# relay.net
KiCad netlist of a schematic drawn in EAGLE
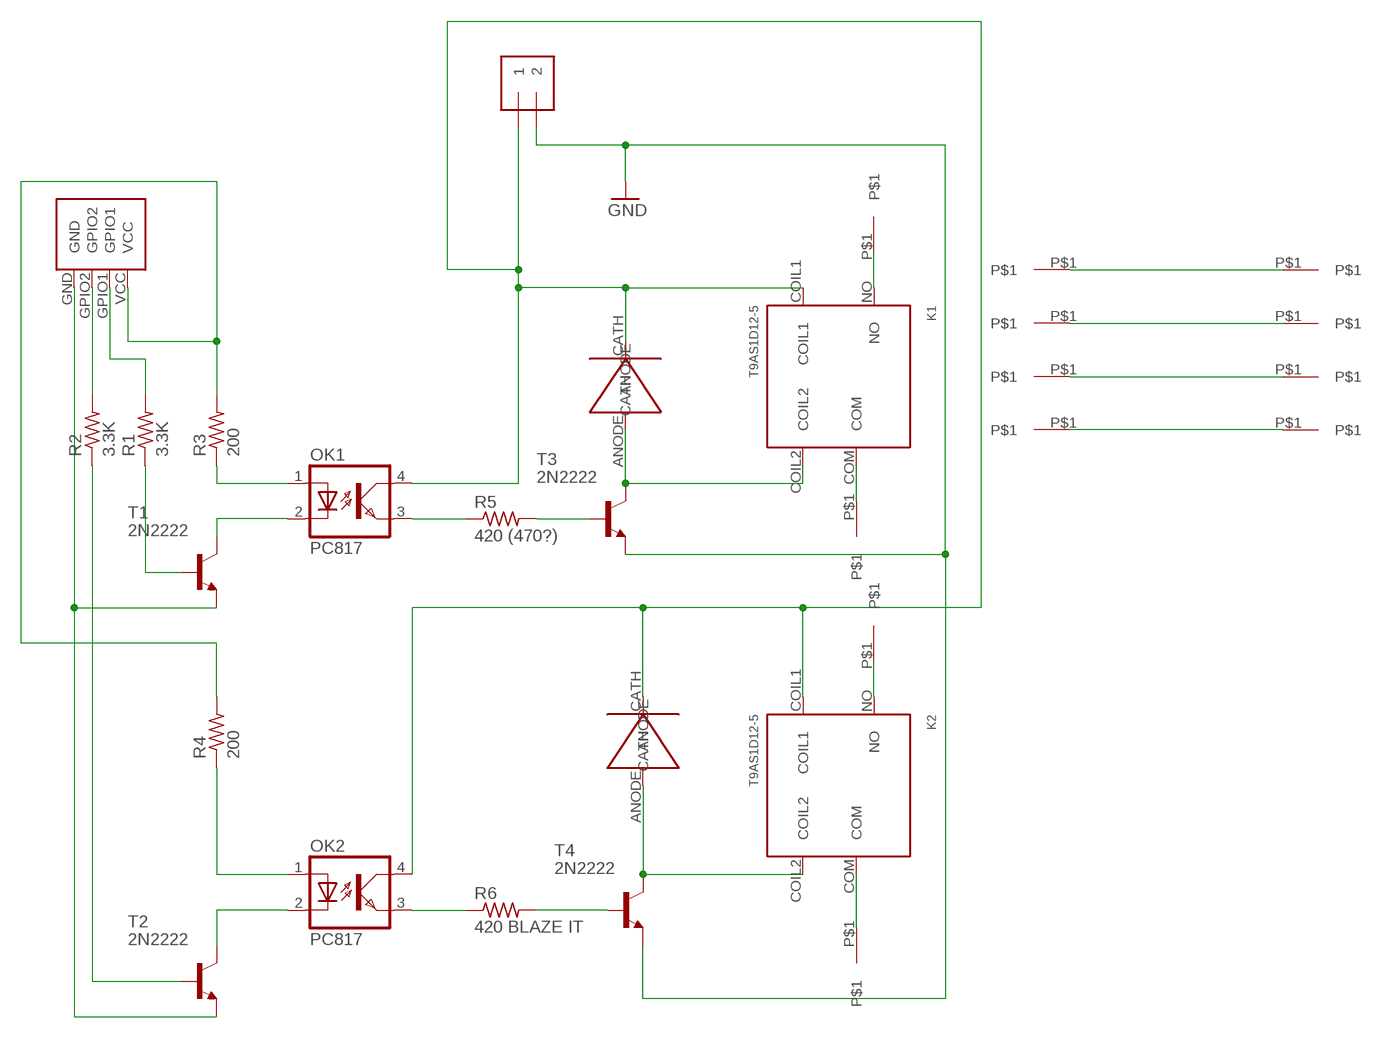
[diagram p0: schematic, sheet 1]

(export (version "E")
  (design (tool "Eeschema 10.0.6"))
  (components
    (comp (ref "J1")
      (value "1X2-3.5MM")
      (footprint "eagle-import:1X2-3.5MM")
      (libsource (lib "eagle-import") (part "1X2-3.5MM"))
    )
    (comp (ref "K1")
      (value "T9AS1D12-5")
      (footprint "eagle-import:T9AS1D12-5")
      (libsource (lib "eagle-import") (part "T9AS1D12-5"))
    )
    (comp (ref "K2")
      (value "T9AS1D12-5")
      (footprint "eagle-import:T9AS1D12-5")
      (libsource (lib "eagle-import") (part "T9AS1D12-5"))
    )
    (comp (ref "OK1")
      (value "PC817")
      (footprint "eagle-import:DIL04")
      (fields (field (name "MPN") "PC817X4J000F"))
      (libsource (lib "eagle-import") (part "PC817"))
    )
    (comp (ref "OK2")
      (value "PC817")
      (footprint "eagle-import:DIL04")
      (fields (field (name "MPN") "PC817X4J000F"))
      (libsource (lib "eagle-import") (part "PC817"))
    )
    (comp (ref "R1")
      (value "3.3K")
      (footprint "eagle-import:R0805")
      (libsource (lib "eagle-import") (part "R-US_R0805"))
    )
    (comp (ref "R2")
      (value "3.3K")
      (footprint "eagle-import:R0805")
      (libsource (lib "eagle-import") (part "R-US_R0805"))
    )
    (comp (ref "R3")
      (value "200")
      (footprint "eagle-import:R0805")
      (libsource (lib "eagle-import") (part "R-US_R0805"))
    )
    (comp (ref "R4")
      (value "200")
      (footprint "eagle-import:R0805")
      (libsource (lib "eagle-import") (part "R-US_R0805"))
    )
    (comp (ref "R5")
      (value "420 (470?)")
      (footprint "eagle-import:R0805")
      (libsource (lib "eagle-import") (part "R-US_R0805"))
    )
    (comp (ref "R6")
      (value "420 BLAZE IT")
      (footprint "eagle-import:R0805")
      (libsource (lib "eagle-import") (part "R-US_R0805"))
    )
    (comp (ref "T1")
      (value "2N2222")
      (footprint "eagle-import:TO92-EBC-OVAL")
      (libsource (lib "eagle-import") (part "2N2222"))
    )
    (comp (ref "T2")
      (value "2N2222")
      (footprint "eagle-import:TO92-EBC-OVAL")
      (libsource (lib "eagle-import") (part "2N2222"))
    )
    (comp (ref "T3")
      (value "2N2222")
      (footprint "eagle-import:TO92-EBC-OVAL")
      (libsource (lib "eagle-import") (part "2N2222"))
    )
    (comp (ref "T4")
      (value "2N2222")
      (footprint "eagle-import:TO92-EBC-OVAL")
      (libsource (lib "eagle-import") (part "2N2222"))
    )
    (comp (ref "U$1")
      (value "MTA-156")
      (footprint "eagle-import:MTA-156_HEADER")
      (libsource (lib "eagle-import") (part "MTA-156"))
    )
    (comp (ref "U$2")
      (value "VTB8441BH")
      (footprint "eagle-import:VTB8441BH")
      (libsource (lib "eagle-import") (part "VTB8441BH"))
    )
    (comp (ref "U$3")
      (value "VTB8441BH")
      (footprint "eagle-import:VTB8441BH")
      (libsource (lib "eagle-import") (part "VTB8441BH"))
    )
    (comp (ref "U$4")
      (value "MAIN")
      (footprint "eagle-import:MAIN")
      (libsource (lib "eagle-import") (part "MAIN"))
    )
    (comp (ref "U$5")
      (value "MAIN")
      (footprint "eagle-import:MAIN")
      (libsource (lib "eagle-import") (part "MAIN"))
    )
    (comp (ref "U$6")
      (value "MAIN")
      (footprint "eagle-import:MAIN")
      (libsource (lib "eagle-import") (part "MAIN"))
    )
    (comp (ref "U$7")
      (value "MAIN")
      (footprint "eagle-import:MAIN")
      (libsource (lib "eagle-import") (part "MAIN"))
    )
    (comp (ref "U$8")
      (value "MAIN")
      (footprint "eagle-import:MAIN")
      (libsource (lib "eagle-import") (part "MAIN"))
    )
    (comp (ref "U$9")
      (value "MAIN")
      (footprint "eagle-import:MAIN")
      (libsource (lib "eagle-import") (part "MAIN"))
    )
    (comp (ref "U$10")
      (value "MAIN")
      (footprint "eagle-import:MAIN")
      (libsource (lib "eagle-import") (part "MAIN"))
    )
    (comp (ref "U$11")
      (value "MAIN")
      (footprint "eagle-import:MAIN")
      (libsource (lib "eagle-import") (part "MAIN"))
    )
    (comp (ref "U$12")
      (value "MAIN")
      (footprint "eagle-import:MAIN")
      (libsource (lib "eagle-import") (part "MAIN"))
    )
    (comp (ref "U$13")
      (value "MAIN")
      (footprint "eagle-import:MAIN")
      (libsource (lib "eagle-import") (part "MAIN"))
    )
    (comp (ref "U$14")
      (value "MAIN")
      (footprint "eagle-import:MAIN")
      (libsource (lib "eagle-import") (part "MAIN"))
    )
    (comp (ref "U$15")
      (value "MAIN")
      (footprint "eagle-import:MAIN")
      (libsource (lib "eagle-import") (part "MAIN"))
    )
  )
  (nets
    (net (code "1") (name "GND") (class "Default")
      (node (ref "J1") (pin "2") (pinfunction "2_2") (pintype "passive"))
      (node (ref "T3") (pin "E") (pinfunction "E_E") (pintype "passive"))
      (node (ref "T4") (pin "E") (pinfunction "E_E") (pintype "passive"))
    )
    (net (code "2") (name "Net-(K1-PadCOIL2)") (class "Default")
      (node (ref "K1") (pin "COIL2") (pinfunction "COIL2_COIL2") (pintype "bidirectional"))
      (node (ref "T3") (pin "C") (pinfunction "C_C") (pintype "passive"))
      (node (ref "U$2") (pin "ANODE") (pinfunction "ANODE_ANODE") (pintype "bidirectional"))
    )
    (net (code "3") (name "Net-(K1-PadCOM)") (class "Default")
      (node (ref "K1") (pin "COM") (pinfunction "COM_COM") (pintype "bidirectional"))
      (node (ref "U$5") (pin "P$1") (pinfunction "P$1_P$1") (pintype "bidirectional"))
    )
    (net (code "4") (name "Net-(K1-PadNO)") (class "Default")
      (node (ref "K1") (pin "NO") (pinfunction "NO_NO") (pintype "bidirectional"))
      (node (ref "U$4") (pin "P$1") (pinfunction "P$1_P$1") (pintype "bidirectional"))
    )
    (net (code "5") (name "Net-(K2-PadCOIL2)") (class "Default")
      (node (ref "K2") (pin "COIL2") (pinfunction "COIL2_COIL2") (pintype "bidirectional"))
      (node (ref "T4") (pin "C") (pinfunction "C_C") (pintype "passive"))
      (node (ref "U$3") (pin "ANODE") (pinfunction "ANODE_ANODE") (pintype "bidirectional"))
    )
    (net (code "6") (name "Net-(K2-PadCOM)") (class "Default")
      (node (ref "K2") (pin "COM") (pinfunction "COM_COM") (pintype "bidirectional"))
      (node (ref "U$7") (pin "P$1") (pinfunction "P$1_P$1") (pintype "bidirectional"))
    )
    (net (code "7") (name "Net-(K2-PadNO)") (class "Default")
      (node (ref "K2") (pin "NO") (pinfunction "NO_NO") (pintype "bidirectional"))
      (node (ref "U$6") (pin "P$1") (pinfunction "P$1_P$1") (pintype "bidirectional"))
    )
    (net (code "8") (name "Net-(OK1-A)") (class "Default")
      (node (ref "OK1") (pin "1") (pinfunction "A_1") (pintype "passive"))
      (node (ref "R3") (pin "1") (pinfunction "1_1") (pintype "passive"))
    )
    (net (code "9") (name "Net-(OK1-C)") (class "Default")
      (node (ref "OK1") (pin "2") (pinfunction "C_2") (pintype "passive"))
      (node (ref "T1") (pin "C") (pinfunction "C_C") (pintype "passive"))
    )
    (net (code "10") (name "Net-(OK1-COL)") (class "Default")
      (node (ref "J1") (pin "1") (pinfunction "1_1") (pintype "passive"))
      (node (ref "K1") (pin "COIL1") (pinfunction "COIL1_COIL1") (pintype "bidirectional"))
      (node (ref "K2") (pin "COIL1") (pinfunction "COIL1_COIL1") (pintype "bidirectional"))
      (node (ref "OK1") (pin "4") (pinfunction "COL_4") (pintype "passive"))
      (node (ref "OK2") (pin "4") (pinfunction "COL_4") (pintype "passive"))
      (node (ref "U$2") (pin "CATH") (pinfunction "CATH_CATH") (pintype "bidirectional"))
      (node (ref "U$3") (pin "CATH") (pinfunction "CATH_CATH") (pintype "bidirectional"))
    )
    (net (code "11") (name "Net-(OK1-EMIT)") (class "Default")
      (node (ref "OK1") (pin "3") (pinfunction "EMIT_3") (pintype "passive"))
      (node (ref "R5") (pin "1") (pinfunction "1_1") (pintype "passive"))
    )
    (net (code "12") (name "Net-(OK2-A)") (class "Default")
      (node (ref "OK2") (pin "1") (pinfunction "A_1") (pintype "passive"))
      (node (ref "R4") (pin "1") (pinfunction "1_1") (pintype "passive"))
    )
    (net (code "13") (name "Net-(OK2-C)") (class "Default")
      (node (ref "OK2") (pin "2") (pinfunction "C_2") (pintype "passive"))
      (node (ref "T2") (pin "C") (pinfunction "C_C") (pintype "passive"))
    )
    (net (code "14") (name "Net-(OK2-EMIT)") (class "Default")
      (node (ref "OK2") (pin "3") (pinfunction "EMIT_3") (pintype "passive"))
      (node (ref "R6") (pin "1") (pinfunction "1_1") (pintype "passive"))
    )
    (net (code "15") (name "Net-(R1-Pad1)") (class "Default")
      (node (ref "R1") (pin "1") (pinfunction "1_1") (pintype "passive"))
      (node (ref "T1") (pin "B") (pinfunction "B_B") (pintype "passive"))
    )
    (net (code "16") (name "Net-(R1-Pad2)") (class "Default")
      (node (ref "R1") (pin "2") (pinfunction "2_2") (pintype "passive"))
      (node (ref "U$1") (pin "GPIO1") (pinfunction "GPIO1_GPIO1") (pintype "bidirectional"))
    )
    (net (code "17") (name "Net-(R2-Pad1)") (class "Default")
      (node (ref "R2") (pin "1") (pinfunction "1_1") (pintype "passive"))
      (node (ref "T2") (pin "B") (pinfunction "B_B") (pintype "passive"))
    )
    (net (code "18") (name "Net-(R2-Pad2)") (class "Default")
      (node (ref "R2") (pin "2") (pinfunction "2_2") (pintype "passive"))
      (node (ref "U$1") (pin "GPIO2") (pinfunction "GPIO2_GPIO2") (pintype "bidirectional"))
    )
    (net (code "19") (name "Net-(R3-Pad2)") (class "Default")
      (node (ref "R3") (pin "2") (pinfunction "2_2") (pintype "passive"))
      (node (ref "R4") (pin "2") (pinfunction "2_2") (pintype "passive"))
      (node (ref "U$1") (pin "VCC") (pinfunction "VCC_VCC") (pintype "power_in"))
    )
    (net (code "20") (name "Net-(R5-Pad2)") (class "Default")
      (node (ref "R5") (pin "2") (pinfunction "2_2") (pintype "passive"))
      (node (ref "T3") (pin "B") (pinfunction "B_B") (pintype "passive"))
    )
    (net (code "21") (name "Net-(R6-Pad2)") (class "Default")
      (node (ref "R6") (pin "2") (pinfunction "2_2") (pintype "passive"))
      (node (ref "T4") (pin "B") (pinfunction "B_B") (pintype "passive"))
    )
    (net (code "22") (name "Net-(T1-PadE)") (class "Default")
      (node (ref "T1") (pin "E") (pinfunction "E_E") (pintype "passive"))
      (node (ref "T2") (pin "E") (pinfunction "E_E") (pintype "passive"))
      (node (ref "U$1") (pin "GND") (pinfunction "GND_GND") (pintype "power_in"))
    )
    (net (code "23") (name "Net-(U$10-PadP$1)") (class "Default")
      (node (ref "U$10") (pin "P$1") (pinfunction "P$1_P$1") (pintype "bidirectional"))
      (node (ref "U$8") (pin "P$1") (pinfunction "P$1_P$1") (pintype "bidirectional"))
    )
    (net (code "24") (name "Net-(U$11-PadP$1)") (class "Default")
      (node (ref "U$11") (pin "P$1") (pinfunction "P$1_P$1") (pintype "bidirectional"))
      (node (ref "U$9") (pin "P$1") (pinfunction "P$1_P$1") (pintype "bidirectional"))
    )
    (net (code "25") (name "Net-(U$12-PadP$1)") (class "Default")
      (node (ref "U$12") (pin "P$1") (pinfunction "P$1_P$1") (pintype "bidirectional"))
      (node (ref "U$13") (pin "P$1") (pinfunction "P$1_P$1") (pintype "bidirectional"))
    )
    (net (code "26") (name "Net-(U$14-PadP$1)") (class "Default")
      (node (ref "U$14") (pin "P$1") (pinfunction "P$1_P$1") (pintype "bidirectional"))
      (node (ref "U$15") (pin "P$1") (pinfunction "P$1_P$1") (pintype "bidirectional"))
    )
  )
)
